# 3_3V_LDO_SUPPLY.net
KiCad netlist of a schematic drawn in Altium Designer
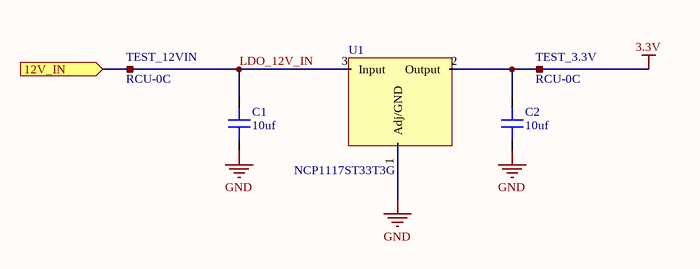
[diagram p0: 3.3V_LDO_SUPPLY.SchDoc]

(export (version "E")
  (design (tool "Eeschema 10.0.6"))
  (components
    (comp (ref "C1")
      (value "10uf")
      (footprint "CAP 0603/1608")
      (fields
        (field (name "Comment") "Capacitor MLCC 10uf 16V CAP 0603/1608")
        (field (name "CREATED_BY") "Nick Mah")
      )
      (libsource (lib "Altium-Lib") (part "Capacitor"))
    )
    (comp (ref "C2")
      (value "10uf")
      (footprint "CAP 0603/1608")
      (fields
        (field (name "Comment") "Capacitor MLCC 10uf 16V CAP 0603/1608")
        (field (name "CREATED_BY") "Nick Mah")
      )
      (libsource (lib "Altium-Lib") (part "Capacitor"))
    )
    (comp (ref "TEST_3.3V")
      (value "RCU-0C")
      (footprint "RCU-0C")
      (libsource (lib "Altium-Lib") (part "RCU-0C"))
    )
    (comp (ref "TEST_12VIN")
      (value "RCU-0C")
      (footprint "RCU-0C")
      (libsource (lib "Altium-Lib") (part "RCU-0C"))
    )
    (comp (ref "U1")
      (value "NCP1117ST33T3G")
      (footprint "SOT-223-3")
      (description "1.0 A Low Dropout Positive and Adjustable Voltage Regulator")
      (libsource (lib "Altium-Lib") (part "NCP1117ST33T3G"))
    )
  )
  (nets
    (net (code "1") (name "/LDO_12V_IN") (class "Default")
      (node (ref "C1") (pin "2") (pinfunction "2_2") (pintype "passive"))
      (node (ref "TEST_12VIN") (pin "1") (pintype "passive"))
      (node (ref "U1") (pin "3") (pinfunction "Input_3") (pintype "input"))
    )
    (net (code "2") (name "3.3V") (class "Default")
      (node (ref "C2") (pin "2") (pinfunction "2_2") (pintype "passive"))
      (node (ref "TEST_3.3V") (pin "1") (pintype "passive"))
      (node (ref "U1") (pin "2") (pinfunction "Output_2") (pintype "input"))
    )
    (net (code "3") (name "GND") (class "Default")
      (node (ref "C1") (pin "1") (pinfunction "1_1") (pintype "passive"))
      (node (ref "C2") (pin "1") (pinfunction "1_1") (pintype "passive"))
      (node (ref "U1") (pin "1") (pinfunction "Adj/GND_1") (pintype "input"))
    )
  )
)
